# Motor_Driver.net
KiCad netlist of a schematic drawn in Altium Designer
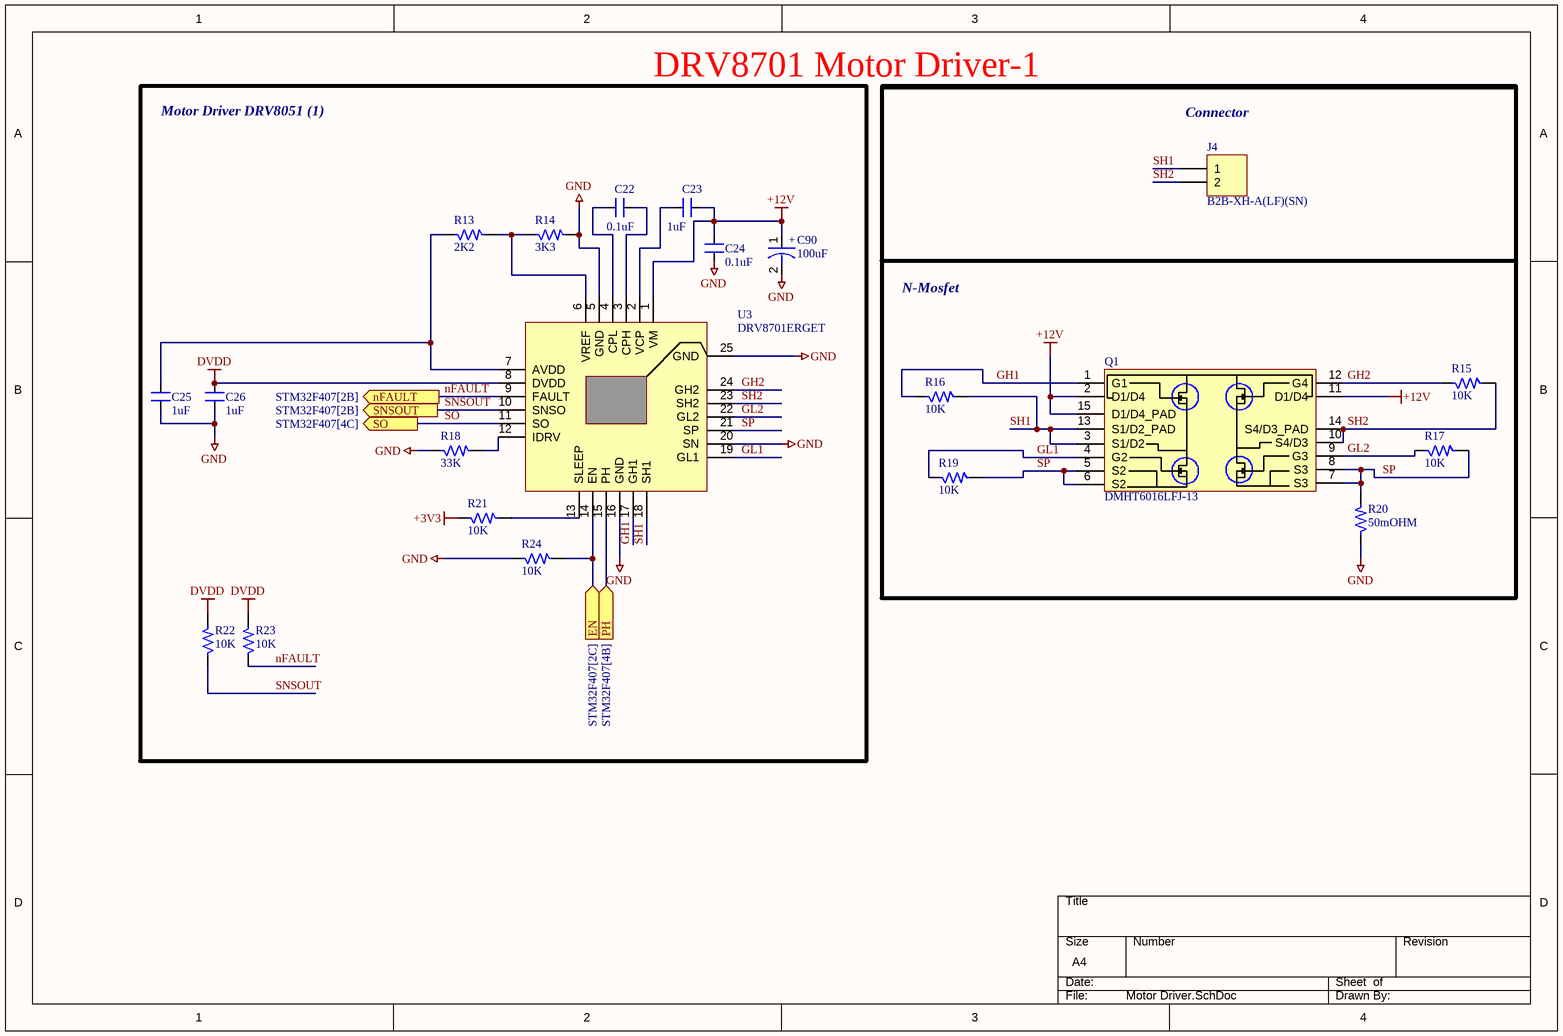
[diagram p0: Motor Driver.SchDoc]

(export (version "E")
  (design (tool "Eeschema 10.0.6"))
  (components
    (comp (ref "C22")
      (value "0.1uF")
      (footprint "CAP_0805")
      (description "0.1µF ±5% 50V Ceramic Capacitor X7R 0805 (2012 Metric)")
      (fields
        (field (name "MANUFACTURER") "AVX Corporation")
        (field (name "MANUFACTURER PART NUMBER") "08055C104JAT4A")
      )
      (libsource (lib "ESTEEMPCBLIB") (part "CAP_0.1uF-50V-5%-0805"))
    )
    (comp (ref "C23")
      (value "1uF")
      (footprint "CAP_0805")
      (description "1µF ±5% 50V Ceramic Capacitor X7R 0805 (2012 Metric)")
      (fields
        (field (name "MANUFACTURER") "Samsung")
        (field (name "MANUFACTURER PART NUMBER") "CC0805JKX7R9BB105")
      )
      (libsource (lib "ESTEEMPCBLIB") (part "CAP_1uF-50V-5%-0805"))
    )
    (comp (ref "C24")
      (value "0.1uF")
      (footprint "CAP_0805")
      (description "0.1µF ±5% 50V Ceramic Capacitor X7R 0805 (2012 Metric)")
      (fields
        (field (name "MANUFACTURER") "AVX Corporation")
        (field (name "MANUFACTURER PART NUMBER") "08055C104JAT4A")
      )
      (libsource (lib "ESTEEMPCBLIB") (part "CAP_0.1uF-50V-5%-0805"))
    )
    (comp (ref "C25")
      (value "1uF")
      (footprint "CAP_0805")
      (description "1µF ±5% 50V Ceramic Capacitor X7R 0805 (2012 Metric)")
      (fields
        (field (name "MANUFACTURER") "Samsung")
        (field (name "MANUFACTURER PART NUMBER") "CC0805JKX7R9BB105")
      )
      (libsource (lib "ESTEEMPCBLIB") (part "CAP_1uF-50V-5%-0805"))
    )
    (comp (ref "C26")
      (value "1uF")
      (footprint "CAP_0805")
      (description "1µF ±5% 50V Ceramic Capacitor X7R 0805 (2012 Metric)")
      (fields
        (field (name "MANUFACTURER") "Samsung")
        (field (name "MANUFACTURER PART NUMBER") "CC0805JKX7R9BB105")
      )
      (libsource (lib "ESTEEMPCBLIB") (part "CAP_1uF-50V-5%-0805"))
    )
    (comp (ref "C90")
      (value "100uF")
      (footprint "ACAP_P305_D393_H393_RAD")
      (description "100µF 50V Aluminum Polymer Capacitor Radial, Can - SMD 28mOhm 4000 Hrs @ 125°C")
      (fields
        (field (name "MANUFACTURER") "Nichicon")
        (field (name "MANUFACTURER PART NUMBER") "GYA1H101MCQ1GS")
      )
      (libsource (lib "ESTEEMPCBLIB") (part "CAP-P_100uF-50V-20%-RAD"))
    )
    (comp (ref "J4")
      (value "B2B-XH-A(LF)(SN)")
      (footprint "CON2_100_B2B-XH-A_TH_ST")
      (description "2 Pins, 1 Row 2.54mm Pitch, Straight Connector, male")
      (fields (field (name "MANUFACTURER") "JST") (field (name "MATING PART NUMBER") "XHP-2"))
      (libsource (lib "ESTEEMPCBLIB") (part "CON-PLG_2X1-100-ST-TH"))
    )
    (comp (ref "Q1")
      (value "DMHT6016LFJ-13")
      (footprint "DFN5045-12_33_212_27X15_SMD_1")
      (description "Mosfet Array 4 N-Channel 14.8A (Ta) Surface Mount V-DFN5045-12")
      (fields (field (name "MANUFACTURER") "ON Semiconductor"))
      (libsource (lib "ESTEEMPCBLIB") (part "MOSFET-N_60V-14.8A-V-DFN5045-12"))
    )
    (comp (ref "R13")
      (value "2K2")
      (footprint "RES_0603")
      (description "2.2 kOhms ±5% 0.1W, 1/10W Chip Resistor 0603 (1608 Metric) Automotive AEC-Q200 Thick Film")
      (fields
        (field (name "MANUFACTURER") "Stackpole Electronics")
        (field (name "MANUFACTURER PART NUMBER") "ERJ-3GEYJ222V")
      )
      (libsource (lib "ESTEEMPCBLIB") (part "RES_2K2-0.1W-5%-0603"))
    )
    (comp (ref "R14")
      (value "3K3")
      (footprint "RES_0603")
      (description "3.3 kOhms ±1% 0.1W, 1/10W Chip Resistor 0603 (1608 Metric) Automotive AEC-Q200 Thick Film")
      (fields (field (name "MANUFACTURER") "Wilson") (field (name "MANUFACTURER PART NUMBER") "WR06X3301FTL"))
      (libsource (lib "ESTEEMPCBLIB") (part "RES_3.3K-0.1W-1%-0603"))
    )
    (comp (ref "R15")
      (value "10K")
      (footprint "RES_0603")
      (description "10 kOhms ±1% 0.1W, 1/10W Chip Resistor 0603 (1608 Metric) Automotive AEC-Q200 Thick Film")
      (fields (field (name "MANUFACTURER") "Walsin") (field (name "MANUFACTURER PART NUMBER") "WR06X1002FTL"))
      (libsource (lib "ESTEEMPCBLIB") (part "RES_10K-0.1W-1%-0603"))
    )
    (comp (ref "R16")
      (value "10K")
      (footprint "RES_0603")
      (description "10 kOhms ±1% 0.1W, 1/10W Chip Resistor 0603 (1608 Metric) Automotive AEC-Q200 Thick Film")
      (fields (field (name "MANUFACTURER") "Walsin") (field (name "MANUFACTURER PART NUMBER") "WR06X1002FTL"))
      (libsource (lib "ESTEEMPCBLIB") (part "RES_10K-0.1W-1%-0603"))
    )
    (comp (ref "R17")
      (value "10K")
      (footprint "RES_0603")
      (description "10 kOhms ±1% 0.1W, 1/10W Chip Resistor 0603 (1608 Metric) Automotive AEC-Q200 Thick Film")
      (fields (field (name "MANUFACTURER") "Walsin") (field (name "MANUFACTURER PART NUMBER") "WR06X1002FTL"))
      (libsource (lib "ESTEEMPCBLIB") (part "RES_10K-0.1W-1%-0603"))
    )
    (comp (ref "R18")
      (value "33K")
      (footprint "RES_0805")
      (fields
        (field (name "MANUFACTURER") "Vishay BCcomponents")
        (field (name "MANUFACTURER PART NUMBER") "CRG0805F33K")
      )
      (libsource (lib "ESTEEMPCBLIB") (part "RES_33K-0.125W-1%-0805"))
    )
    (comp (ref "R19")
      (value "10K")
      (footprint "RES_0603")
      (description "10 kOhms ±1% 0.1W, 1/10W Chip Resistor 0603 (1608 Metric) Automotive AEC-Q200 Thick Film")
      (fields (field (name "MANUFACTURER") "Walsin") (field (name "MANUFACTURER PART NUMBER") "WR06X1002FTL"))
      (libsource (lib "ESTEEMPCBLIB") (part "RES_10K-0.1W-1%-0603"))
    )
    (comp (ref "R20")
      (value "50mOHM")
      (footprint "RES_2512")
      (fields
        (field (name "MANUFACTURER") "Yageo")
        (field (name "MANUFACTURER PART NUMBER") "PA2512FKF7W0R05E")
      )
      (libsource (lib "ESTEEMPCBLIB") (part "RES_50mOhm-2W-1%-2512"))
    )
    (comp (ref "R21")
      (value "10K")
      (footprint "RES_0603")
      (description "10 kOhms ±1% 0.1W, 1/10W Chip Resistor 0603 (1608 Metric) Automotive AEC-Q200 Thick Film")
      (fields (field (name "MANUFACTURER") "Walsin") (field (name "MANUFACTURER PART NUMBER") "WR06X1002FTL"))
      (libsource (lib "ESTEEMPCBLIB") (part "RES_10K-0.1W-1%-0603"))
    )
    (comp (ref "R22")
      (value "10K")
      (footprint "RES_0603")
      (description "10 kOhms ±1% 0.1W, 1/10W Chip Resistor 0603 (1608 Metric) Automotive AEC-Q200 Thick Film")
      (fields (field (name "MANUFACTURER") "Walsin") (field (name "MANUFACTURER PART NUMBER") "WR06X1002FTL"))
      (libsource (lib "ESTEEMPCBLIB") (part "RES_10K-0.1W-1%-0603"))
    )
    (comp (ref "R23")
      (value "10K")
      (footprint "RES_0603")
      (description "10 kOhms ±1% 0.1W, 1/10W Chip Resistor 0603 (1608 Metric) Automotive AEC-Q200 Thick Film")
      (fields (field (name "MANUFACTURER") "Walsin") (field (name "MANUFACTURER PART NUMBER") "WR06X1002FTL"))
      (libsource (lib "ESTEEMPCBLIB") (part "RES_10K-0.1W-1%-0603"))
    )
    (comp (ref "R24")
      (value "10K")
      (footprint "RES_0603")
      (description "10 kOhms ±1% 0.1W, 1/10W Chip Resistor 0603 (1608 Metric) Automotive AEC-Q200 Thick Film")
      (fields (field (name "MANUFACTURER") "Walsin") (field (name "MANUFACTURER PART NUMBER") "WR06X1002FTL"))
      (libsource (lib "ESTEEMPCBLIB") (part "RES_10K-0.1W-1%-0603"))
    )
    (comp (ref "U3")
      (value "DRV8701ERGET")
      (footprint "VFQFN24_19.6_196_12X32_SMD_1")
      (description "Motor Driver Power MOSFET Parallel 24-VQFN (4x4)")
      (fields (field (name "MANUFACTURER") "Texas Instruments"))
      (libsource (lib "ESTEEMPCBLIB") (part "IC_DRV8701ERGET"))
    )
  )
  (nets
    (net (code "1") (name "+3V3") (class "Default")
      (node (ref "R21") (pin "1") (pinfunction "1_1") (pintype "passive"))
    )
    (net (code "2") (name "+12V") (class "Default")
      (node (ref "C23") (pin "2") (pinfunction "2_2") (pintype "passive"))
      (node (ref "C24") (pin "2") (pinfunction "2_2") (pintype "passive"))
      (node (ref "C90") (pin "1") (pinfunction "1_1") (pintype "passive"))
      (node (ref "Q1") (pin "11") (pinfunction "D1/D4_11") (pintype "passive"))
      (node (ref "Q1") (pin "15") (pinfunction "D1/D4_PAD_15") (pintype "passive"))
      (node (ref "Q1") (pin "2") (pinfunction "D1/D4_2") (pintype "passive"))
      (node (ref "U3") (pin "1") (pinfunction "VM_1") (pintype "passive"))
    )
    (net (code "3") (name "/EN") (class "Default")
      (node (ref "R24") (pin "2") (pinfunction "2_2") (pintype "passive"))
      (node (ref "U3") (pin "14") (pinfunction "EN_14") (pintype "passive"))
    )
    (net (code "4") (name "/GH1") (class "Default")
      (node (ref "Q1") (pin "1") (pinfunction "G1_1") (pintype "passive"))
      (node (ref "R16") (pin "1") (pinfunction "1_1") (pintype "passive"))
      (node (ref "U3") (pin "17") (pinfunction "GH1_17") (pintype "passive"))
    )
    (net (code "5") (name "/GH2") (class "Default")
      (node (ref "Q1") (pin "12") (pinfunction "G4_12") (pintype "passive"))
      (node (ref "R15") (pin "1") (pinfunction "1_1") (pintype "passive"))
      (node (ref "U3") (pin "24") (pinfunction "GH2_24") (pintype "passive"))
    )
    (net (code "6") (name "/GL1") (class "Default")
      (node (ref "Q1") (pin "4") (pinfunction "G2_4") (pintype "passive"))
      (node (ref "R19") (pin "1") (pinfunction "1_1") (pintype "passive"))
      (node (ref "U3") (pin "19") (pinfunction "GL1_19") (pintype "passive"))
    )
    (net (code "7") (name "/GL2") (class "Default")
      (node (ref "Q1") (pin "9") (pinfunction "G3_9") (pintype "passive"))
      (node (ref "R17") (pin "1") (pinfunction "1_1") (pintype "passive"))
      (node (ref "U3") (pin "22") (pinfunction "GL2_22") (pintype "passive"))
    )
    (net (code "8") (name "/PH") (class "Default")
      (node (ref "U3") (pin "15") (pinfunction "PH_15") (pintype "passive"))
    )
    (net (code "9") (name "/SH1") (class "Default")
      (node (ref "J4") (pin "1") (pinfunction "1_1") (pintype "passive"))
      (node (ref "Q1") (pin "13") (pinfunction "S1/D2_PAD_13") (pintype "passive"))
      (node (ref "Q1") (pin "3") (pinfunction "S1/D2_3") (pintype "passive"))
      (node (ref "R16") (pin "2") (pinfunction "2_2") (pintype "passive"))
      (node (ref "U3") (pin "18") (pinfunction "SH1_18") (pintype "passive"))
    )
    (net (code "10") (name "/SH2") (class "Default")
      (node (ref "J4") (pin "2") (pinfunction "2_2") (pintype "passive"))
      (node (ref "Q1") (pin "10") (pinfunction "S4/D3_10") (pintype "passive"))
      (node (ref "Q1") (pin "14") (pinfunction "S4/D3_PAD_14") (pintype "passive"))
      (node (ref "R15") (pin "2") (pinfunction "2_2") (pintype "passive"))
      (node (ref "U3") (pin "23") (pinfunction "SH2_23") (pintype "passive"))
    )
    (net (code "11") (name "/SNSOUT") (class "Default")
      (node (ref "R22") (pin "1") (pinfunction "1_1") (pintype "passive"))
      (node (ref "U3") (pin "10") (pinfunction "SNSO_10") (pintype "passive"))
    )
    (net (code "12") (name "/SO") (class "Default")
      (node (ref "U3") (pin "11") (pinfunction "SO_11") (pintype "passive"))
    )
    (net (code "13") (name "/SP") (class "Default")
      (node (ref "Q1") (pin "5") (pinfunction "S2_5") (pintype "passive"))
      (node (ref "Q1") (pin "6") (pinfunction "S2_6") (pintype "passive"))
      (node (ref "Q1") (pin "7") (pinfunction "S3_7") (pintype "passive"))
      (node (ref "Q1") (pin "8") (pinfunction "S3_8") (pintype "passive"))
      (node (ref "R17") (pin "2") (pinfunction "2_2") (pintype "passive"))
      (node (ref "R19") (pin "2") (pinfunction "2_2") (pintype "passive"))
      (node (ref "R20") (pin "2") (pinfunction "2_2") (pintype "passive"))
      (node (ref "U3") (pin "21") (pinfunction "SP_21") (pintype "passive"))
    )
    (net (code "14") (name "/nFAULT") (class "Default")
      (node (ref "R23") (pin "1") (pinfunction "1_1") (pintype "passive"))
      (node (ref "U3") (pin "9") (pinfunction "FAULT_9") (pintype "passive"))
    )
    (net (code "15") (name "DVDD") (class "Default")
      (node (ref "C26") (pin "2") (pinfunction "2_2") (pintype "passive"))
      (node (ref "R22") (pin "2") (pinfunction "2_2") (pintype "passive"))
      (node (ref "R23") (pin "2") (pinfunction "2_2") (pintype "passive"))
      (node (ref "U3") (pin "8") (pinfunction "DVDD_8") (pintype "passive"))
    )
    (net (code "16") (name "GND") (class "Default")
      (node (ref "C24") (pin "1") (pinfunction "1_1") (pintype "passive"))
      (node (ref "C25") (pin "1") (pinfunction "1_1") (pintype "passive"))
      (node (ref "C26") (pin "1") (pinfunction "1_1") (pintype "passive"))
      (node (ref "C90") (pin "2") (pinfunction "2_2") (pintype "passive"))
      (node (ref "R14") (pin "2") (pinfunction "2_2") (pintype "passive"))
      (node (ref "R18") (pin "1") (pinfunction "1_1") (pintype "passive"))
      (node (ref "R20") (pin "1") (pinfunction "1_1") (pintype "passive"))
      (node (ref "R24") (pin "1") (pinfunction "1_1") (pintype "passive"))
      (node (ref "U3") (pin "16") (pinfunction "GND_16") (pintype "passive"))
      (node (ref "U3") (pin "20") (pinfunction "SN_20") (pintype "passive"))
      (node (ref "U3") (pin "25") (pinfunction "GND_25") (pintype "passive"))
      (node (ref "U3") (pin "5") (pinfunction "GND_5") (pintype "passive"))
    )
    (net (code "17") (name "Net-(U3-AVDD)") (class "Default")
      (node (ref "C25") (pin "2") (pinfunction "2_2") (pintype "passive"))
      (node (ref "R13") (pin "1") (pinfunction "1_1") (pintype "passive"))
      (node (ref "U3") (pin "7") (pinfunction "AVDD_7") (pintype "passive"))
    )
    (net (code "18") (name "Net-(U3-CPH)") (class "Default")
      (node (ref "C22") (pin "1") (pinfunction "1_1") (pintype "passive"))
      (node (ref "U3") (pin "3") (pinfunction "CPH_3") (pintype "passive"))
    )
    (net (code "19") (name "Net-(U3-CPL)") (class "Default")
      (node (ref "C22") (pin "2") (pinfunction "2_2") (pintype "passive"))
      (node (ref "U3") (pin "4") (pinfunction "CPL_4") (pintype "passive"))
    )
    (net (code "20") (name "Net-(U3-IDRV)") (class "Default")
      (node (ref "R18") (pin "2") (pinfunction "2_2") (pintype "passive"))
      (node (ref "U3") (pin "12") (pinfunction "IDRV_12") (pintype "passive"))
    )
    (net (code "21") (name "Net-(U3-SLEEP)") (class "Default")
      (node (ref "R21") (pin "2") (pinfunction "2_2") (pintype "passive"))
      (node (ref "U3") (pin "13") (pinfunction "SLEEP_13") (pintype "passive"))
    )
    (net (code "22") (name "Net-(U3-VCP)") (class "Default")
      (node (ref "C23") (pin "1") (pinfunction "1_1") (pintype "passive"))
      (node (ref "U3") (pin "2") (pinfunction "VCP_2") (pintype "passive"))
    )
    (net (code "23") (name "Net-(U3-VREF)") (class "Default")
      (node (ref "R13") (pin "2") (pinfunction "2_2") (pintype "passive"))
      (node (ref "R14") (pin "1") (pinfunction "1_1") (pintype "passive"))
      (node (ref "U3") (pin "6") (pinfunction "VREF_6") (pintype "passive"))
    )
  )
)
